# schematic.net
KiCad netlist of a schematic drawn in EAGLE
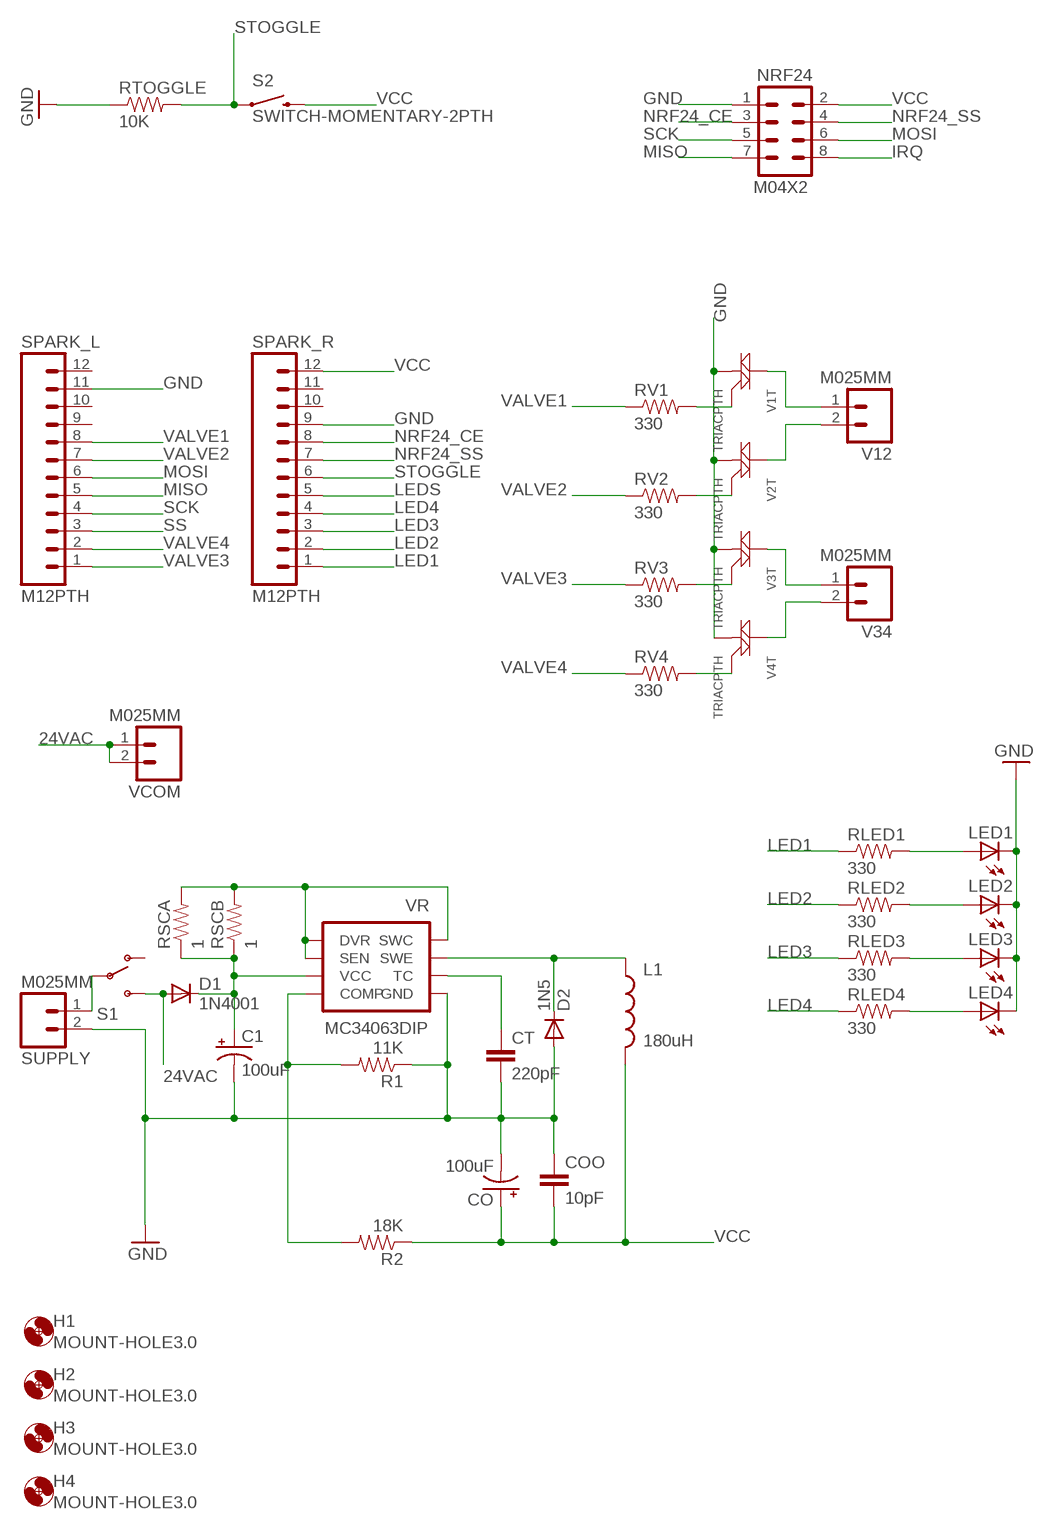
[diagram p0: schematic, sheet 1]

(export (version "E")
  (design (tool "Eeschema 10.0.6"))
  (components
    (comp (ref "C1")
      (value "100uF")
      (footprint "eagle-import:E3,5-8")
      (libsource (lib "eagle-import") (part "CPOL-USE3.5-8"))
    )
    (comp (ref "CO")
      (value "100uF")
      (footprint "eagle-import:CPOL-RADIAL-100UF-25V")
      (libsource (lib "eagle-import") (part "CAP_POLPTH1"))
    )
    (comp (ref "COO")
      (value "10pF")
      (footprint "eagle-import:CAP-PTH-5MM")
      (libsource (lib "eagle-import") (part "CAPPTH1"))
    )
    (comp (ref "CT")
      (value "220pF")
      (footprint "eagle-import:CAP-PTH-5MM")
      (libsource (lib "eagle-import") (part "CAPPTH1"))
    )
    (comp (ref "D1")
      (value "1N4001")
      (footprint "eagle-import:DIODE-1N4001")
      (libsource (lib "eagle-import") (part "DIODEPTH"))
    )
    (comp (ref "D2")
      (value "1N5")
      (footprint "eagle-import:DIODE-1N4001")
      (libsource (lib "eagle-import") (part "DIODEPTH"))
    )
    (comp (ref "H1")
      (value "MOUNT-HOLE3.0")
      (footprint "eagle-import:3,0")
      (libsource (lib "eagle-import") (part "MOUNT-HOLE3.0"))
    )
    (comp (ref "H2")
      (value "MOUNT-HOLE3.0")
      (footprint "eagle-import:3,0")
      (libsource (lib "eagle-import") (part "MOUNT-HOLE3.0"))
    )
    (comp (ref "H3")
      (value "MOUNT-HOLE3.0")
      (footprint "eagle-import:3,0")
      (libsource (lib "eagle-import") (part "MOUNT-HOLE3.0"))
    )
    (comp (ref "H4")
      (value "MOUNT-HOLE3.0")
      (footprint "eagle-import:3,0")
      (libsource (lib "eagle-import") (part "MOUNT-HOLE3.0"))
    )
    (comp (ref "L1")
      (value "180uH")
      (footprint "eagle-import:RLB0912")
      (libsource (lib "eagle-import") (part "INDUCTORRLB0912"))
    )
    (comp (ref "LED1")
      (value "LED3MM")
      (footprint "eagle-import:LED3MM")
      (libsource (lib "eagle-import") (part "LED3MM"))
    )
    (comp (ref "LED2")
      (value "LED3MM")
      (footprint "eagle-import:LED3MM")
      (libsource (lib "eagle-import") (part "LED3MM"))
    )
    (comp (ref "LED3")
      (value "LED3MM")
      (footprint "eagle-import:LED3MM")
      (libsource (lib "eagle-import") (part "LED3MM"))
    )
    (comp (ref "LED4")
      (value "LED3MM")
      (footprint "eagle-import:LED3MM")
      (libsource (lib "eagle-import") (part "LED3MM"))
    )
    (comp (ref "NRF24")
      (value "M04X2")
      (footprint "eagle-import:2X4")
      (libsource (lib "eagle-import") (part "M04X2"))
    )
    (comp (ref "R1")
      (value "11K")
      (footprint "eagle-import:AXIAL-0.3")
      (libsource (lib "eagle-import") (part "RESISTORAXIAL-0.3"))
    )
    (comp (ref "R2")
      (value "18K")
      (footprint "eagle-import:AXIAL-0.3")
      (libsource (lib "eagle-import") (part "RESISTORAXIAL-0.3"))
    )
    (comp (ref "RLED1")
      (value "330")
      (footprint "eagle-import:AXIAL-0.3")
      (libsource (lib "eagle-import") (part "RESISTORAXIAL-0.3"))
    )
    (comp (ref "RLED2")
      (value "330")
      (footprint "eagle-import:AXIAL-0.3")
      (libsource (lib "eagle-import") (part "RESISTORAXIAL-0.3"))
    )
    (comp (ref "RLED3")
      (value "330")
      (footprint "eagle-import:AXIAL-0.3")
      (libsource (lib "eagle-import") (part "RESISTORAXIAL-0.3"))
    )
    (comp (ref "RLED4")
      (value "330")
      (footprint "eagle-import:AXIAL-0.3")
      (libsource (lib "eagle-import") (part "RESISTORAXIAL-0.3"))
    )
    (comp (ref "RSCA")
      (value "1")
      (footprint "eagle-import:AXIAL-0.3")
      (libsource (lib "eagle-import") (part "RESISTORAXIAL-0.3"))
    )
    (comp (ref "RSCB")
      (value "1")
      (footprint "eagle-import:AXIAL-0.3")
      (libsource (lib "eagle-import") (part "RESISTORAXIAL-0.3"))
    )
    (comp (ref "RTOGGLE")
      (value "10K")
      (footprint "eagle-import:AXIAL-0.3")
      (libsource (lib "eagle-import") (part "RESISTORAXIAL-0.3"))
    )
    (comp (ref "RV1")
      (value "330")
      (footprint "eagle-import:AXIAL-0.3")
      (libsource (lib "eagle-import") (part "RESISTORAXIAL-0.3"))
    )
    (comp (ref "RV2")
      (value "330")
      (footprint "eagle-import:AXIAL-0.3")
      (libsource (lib "eagle-import") (part "RESISTORAXIAL-0.3"))
    )
    (comp (ref "RV3")
      (value "330")
      (footprint "eagle-import:AXIAL-0.3")
      (libsource (lib "eagle-import") (part "RESISTORAXIAL-0.3"))
    )
    (comp (ref "RV4")
      (value "330")
      (footprint "eagle-import:AXIAL-0.3")
      (libsource (lib "eagle-import") (part "RESISTORAXIAL-0.3"))
    )
    (comp (ref "S1")
      (value "SWITCH-SPDTPTH")
      (footprint "eagle-import:SWITCH-SPDT")
      (libsource (lib "eagle-import") (part "SWITCH-SPDTPTH"))
    )
    (comp (ref "S2")
      (value "SWITCH-MOMENTARY-2PTH")
      (footprint "eagle-import:TACTILE-PTH")
      (libsource (lib "eagle-import") (part "SWITCH-MOMENTARY-2PTH"))
    )
    (comp (ref "SPARK_L")
      (value "M12PTH")
      (footprint "eagle-import:1X12")
      (libsource (lib "eagle-import") (part "M12PTH"))
    )
    (comp (ref "SPARK_R")
      (value "M12PTH")
      (footprint "eagle-import:1X12")
      (libsource (lib "eagle-import") (part "M12PTH"))
    )
    (comp (ref "SUPPLY")
      (value "M025MM")
      (footprint "eagle-import:SCREWTERMINAL-5MM-2")
      (libsource (lib "eagle-import") (part "M025MM"))
    )
    (comp (ref "V1T")
      (value "TRIACPTH")
      (footprint "eagle-import:TO-92")
      (libsource (lib "eagle-import") (part "TRIACPTH"))
    )
    (comp (ref "V2T")
      (value "TRIACPTH")
      (footprint "eagle-import:TO-92")
      (libsource (lib "eagle-import") (part "TRIACPTH"))
    )
    (comp (ref "V3T")
      (value "TRIACPTH")
      (footprint "eagle-import:TO-92")
      (libsource (lib "eagle-import") (part "TRIACPTH"))
    )
    (comp (ref "V4T")
      (value "TRIACPTH")
      (footprint "eagle-import:TO-92")
      (libsource (lib "eagle-import") (part "TRIACPTH"))
    )
    (comp (ref "V12")
      (value "M025MM")
      (footprint "eagle-import:SCREWTERMINAL-5MM-2")
      (libsource (lib "eagle-import") (part "M025MM"))
    )
    (comp (ref "V34")
      (value "M025MM")
      (footprint "eagle-import:SCREWTERMINAL-5MM-2")
      (libsource (lib "eagle-import") (part "M025MM"))
    )
    (comp (ref "VCOM")
      (value "M025MM")
      (footprint "eagle-import:SCREWTERMINAL-5MM-2")
      (libsource (lib "eagle-import") (part "M025MM"))
    )
    (comp (ref "VR")
      (value "MC34063DIP")
      (footprint "eagle-import:DIP-08")
      (libsource (lib "eagle-import") (part "MC34063DIP"))
    )
  )
  (nets
    (net (code "1") (name "/24VAC") (class "Default")
      (node (ref "D1") (pin "A") (pinfunction "A_A") (pintype "passive"))
      (node (ref "S1") (pin "3") (pinfunction "S_3") (pintype "passive"))
      (node (ref "VCOM") (pin "1") (pinfunction "1_1") (pintype "passive"))
      (node (ref "VCOM") (pin "2") (pinfunction "2_2") (pintype "passive"))
    )
    (net (code "2") (name "/IRQ") (class "Default")
      (node (ref "NRF24") (pin "8") (pinfunction "8_8") (pintype "passive"))
    )
    (net (code "3") (name "/LED1") (class "Default")
      (node (ref "RLED1") (pin "P$1") (pinfunction "1_P$1") (pintype "passive"))
      (node (ref "SPARK_R") (pin "1") (pinfunction "1_1") (pintype "passive"))
    )
    (net (code "4") (name "/LED2") (class "Default")
      (node (ref "RLED2") (pin "P$1") (pinfunction "1_P$1") (pintype "passive"))
      (node (ref "SPARK_R") (pin "2") (pinfunction "2_2") (pintype "passive"))
    )
    (net (code "5") (name "/LED3") (class "Default")
      (node (ref "RLED3") (pin "P$1") (pinfunction "1_P$1") (pintype "passive"))
      (node (ref "SPARK_R") (pin "3") (pinfunction "3_3") (pintype "passive"))
    )
    (net (code "6") (name "/LED4") (class "Default")
      (node (ref "RLED4") (pin "P$1") (pinfunction "1_P$1") (pintype "passive"))
      (node (ref "SPARK_R") (pin "4") (pinfunction "4_4") (pintype "passive"))
    )
    (net (code "7") (name "/LEDS") (class "Default")
      (node (ref "SPARK_R") (pin "5") (pinfunction "5_5") (pintype "passive"))
    )
    (net (code "8") (name "/MISO") (class "Default")
      (node (ref "NRF24") (pin "7") (pinfunction "7_7") (pintype "passive"))
      (node (ref "SPARK_L") (pin "5") (pinfunction "5_5") (pintype "passive"))
    )
    (net (code "9") (name "/MOSI") (class "Default")
      (node (ref "NRF24") (pin "6") (pinfunction "6_6") (pintype "passive"))
      (node (ref "SPARK_L") (pin "6") (pinfunction "6_6") (pintype "passive"))
    )
    (net (code "10") (name "/NRF24_CE") (class "Default")
      (node (ref "NRF24") (pin "3") (pinfunction "3_3") (pintype "passive"))
      (node (ref "SPARK_R") (pin "8") (pinfunction "8_8") (pintype "passive"))
    )
    (net (code "11") (name "/NRF24_SS") (class "Default")
      (node (ref "NRF24") (pin "4") (pinfunction "4_4") (pintype "passive"))
      (node (ref "SPARK_R") (pin "7") (pinfunction "7_7") (pintype "passive"))
    )
    (net (code "12") (name "/SCK") (class "Default")
      (node (ref "NRF24") (pin "5") (pinfunction "5_5") (pintype "passive"))
      (node (ref "SPARK_L") (pin "4") (pinfunction "4_4") (pintype "passive"))
    )
    (net (code "13") (name "/SS") (class "Default")
      (node (ref "SPARK_L") (pin "3") (pinfunction "3_3") (pintype "passive"))
    )
    (net (code "14") (name "/STOGGLE") (class "Default")
      (node (ref "RTOGGLE") (pin "P$2") (pinfunction "2_P$2") (pintype "passive"))
      (node (ref "S2") (pin "1") (pinfunction "1_1") (pintype "passive"))
      (node (ref "SPARK_R") (pin "6") (pinfunction "6_6") (pintype "passive"))
    )
    (net (code "15") (name "/VALVE1") (class "Default")
      (node (ref "RV1") (pin "P$1") (pinfunction "1_P$1") (pintype "passive"))
      (node (ref "SPARK_L") (pin "8") (pinfunction "8_8") (pintype "passive"))
    )
    (net (code "16") (name "/VALVE2") (class "Default")
      (node (ref "RV2") (pin "P$1") (pinfunction "1_P$1") (pintype "passive"))
      (node (ref "SPARK_L") (pin "7") (pinfunction "7_7") (pintype "passive"))
    )
    (net (code "17") (name "/VALVE3") (class "Default")
      (node (ref "RV3") (pin "P$1") (pinfunction "1_P$1") (pintype "passive"))
      (node (ref "SPARK_L") (pin "1") (pinfunction "1_1") (pintype "passive"))
    )
    (net (code "18") (name "/VALVE4") (class "Default")
      (node (ref "RV4") (pin "P$1") (pinfunction "1_P$1") (pintype "passive"))
      (node (ref "SPARK_L") (pin "2") (pinfunction "2_2") (pintype "passive"))
    )
    (net (code "19") (name "/VCC") (class "Default")
      (node (ref "CO") (pin "1") (pinfunction "+_1") (pintype "passive"))
      (node (ref "COO") (pin "2") (pinfunction "2_2") (pintype "passive"))
      (node (ref "L1") (pin "2") (pinfunction "2_2") (pintype "passive"))
      (node (ref "NRF24") (pin "2") (pinfunction "2_2") (pintype "passive"))
      (node (ref "R2") (pin "P$1") (pinfunction "1_P$1") (pintype "passive"))
      (node (ref "S2") (pin "3") (pinfunction "2_3") (pintype "passive"))
      (node (ref "SPARK_R") (pin "12") (pinfunction "12_12") (pintype "passive"))
    )
    (net (code "20") (name "GND") (class "Default")
      (node (ref "C1") (pin "-") (pinfunction "-_-") (pintype "passive"))
      (node (ref "CO") (pin "2") (pinfunction "-_2") (pintype "passive"))
      (node (ref "COO") (pin "1") (pinfunction "1_1") (pintype "passive"))
      (node (ref "CT") (pin "2") (pinfunction "2_2") (pintype "passive"))
      (node (ref "D2") (pin "A") (pinfunction "A_A") (pintype "passive"))
      (node (ref "LED1") (pin "K") (pinfunction "C_K") (pintype "passive"))
      (node (ref "LED2") (pin "K") (pinfunction "C_K") (pintype "passive"))
      (node (ref "LED3") (pin "K") (pinfunction "C_K") (pintype "passive"))
      (node (ref "LED4") (pin "K") (pinfunction "C_K") (pintype "passive"))
      (node (ref "NRF24") (pin "1") (pinfunction "1_1") (pintype "passive"))
      (node (ref "R1") (pin "P$1") (pinfunction "1_P$1") (pintype "passive"))
      (node (ref "RTOGGLE") (pin "P$1") (pinfunction "1_P$1") (pintype "passive"))
      (node (ref "SPARK_L") (pin "11") (pinfunction "11_11") (pintype "passive"))
      (node (ref "SPARK_R") (pin "9") (pinfunction "9_9") (pintype "passive"))
      (node (ref "SUPPLY") (pin "2") (pinfunction "2_2") (pintype "passive"))
      (node (ref "V1T") (pin "1") (pinfunction "M1_1") (pintype "bidirectional"))
      (node (ref "V2T") (pin "1") (pinfunction "M1_1") (pintype "bidirectional"))
      (node (ref "V3T") (pin "1") (pinfunction "M1_1") (pintype "bidirectional"))
      (node (ref "V4T") (pin "1") (pinfunction "M1_1") (pintype "bidirectional"))
      (node (ref "VR") (pin "4") (pinfunction "GND_4") (pintype "bidirectional"))
    )
    (net (code "21") (name "Net-(R1-2)") (class "Default")
      (node (ref "R1") (pin "P$2") (pinfunction "2_P$2") (pintype "passive"))
      (node (ref "R2") (pin "P$2") (pinfunction "2_P$2") (pintype "passive"))
      (node (ref "VR") (pin "5") (pinfunction "COMP_5") (pintype "bidirectional"))
    )
    (net (code "22") (name "Net-(RLED1-2)") (class "Default")
      (node (ref "LED1") (pin "A") (pinfunction "A_A") (pintype "passive"))
      (node (ref "RLED1") (pin "P$2") (pinfunction "2_P$2") (pintype "passive"))
    )
    (net (code "23") (name "Net-(RLED2-2)") (class "Default")
      (node (ref "LED2") (pin "A") (pinfunction "A_A") (pintype "passive"))
      (node (ref "RLED2") (pin "P$2") (pinfunction "2_P$2") (pintype "passive"))
    )
    (net (code "24") (name "Net-(RLED3-2)") (class "Default")
      (node (ref "LED3") (pin "A") (pinfunction "A_A") (pintype "passive"))
      (node (ref "RLED3") (pin "P$2") (pinfunction "2_P$2") (pintype "passive"))
    )
    (net (code "25") (name "Net-(RLED4-2)") (class "Default")
      (node (ref "LED4") (pin "A") (pinfunction "A_A") (pintype "passive"))
      (node (ref "RLED4") (pin "P$2") (pinfunction "2_P$2") (pintype "passive"))
    )
    (net (code "26") (name "Net-(RSCA-1)") (class "Default")
      (node (ref "C1") (pin "+") (pinfunction "+_+") (pintype "passive"))
      (node (ref "D1") (pin "C") (pinfunction "C_C") (pintype "passive"))
      (node (ref "RSCA") (pin "P$1") (pinfunction "1_P$1") (pintype "passive"))
      (node (ref "RSCB") (pin "P$1") (pinfunction "1_P$1") (pintype "passive"))
      (node (ref "VR") (pin "6") (pinfunction "VCC_6") (pintype "bidirectional"))
    )
    (net (code "27") (name "Net-(RSCA-2)") (class "Default")
      (node (ref "RSCA") (pin "P$2") (pinfunction "2_P$2") (pintype "passive"))
      (node (ref "RSCB") (pin "P$2") (pinfunction "2_P$2") (pintype "passive"))
      (node (ref "VR") (pin "1") (pinfunction "SWC_1") (pintype "bidirectional"))
      (node (ref "VR") (pin "7") (pinfunction "SEN_7") (pintype "bidirectional"))
      (node (ref "VR") (pin "8") (pinfunction "DVR_8") (pintype "bidirectional"))
    )
    (net (code "28") (name "Net-(RV1-2)") (class "Default")
      (node (ref "RV1") (pin "P$2") (pinfunction "2_P$2") (pintype "passive"))
      (node (ref "V1T") (pin "2") (pinfunction "G_2") (pintype "bidirectional"))
    )
    (net (code "29") (name "Net-(RV2-2)") (class "Default")
      (node (ref "RV2") (pin "P$2") (pinfunction "2_P$2") (pintype "passive"))
      (node (ref "V2T") (pin "2") (pinfunction "G_2") (pintype "bidirectional"))
    )
    (net (code "30") (name "Net-(RV3-2)") (class "Default")
      (node (ref "RV3") (pin "P$2") (pinfunction "2_P$2") (pintype "passive"))
      (node (ref "V3T") (pin "2") (pinfunction "G_2") (pintype "bidirectional"))
    )
    (net (code "31") (name "Net-(RV4-2)") (class "Default")
      (node (ref "RV4") (pin "P$2") (pinfunction "2_P$2") (pintype "passive"))
      (node (ref "V4T") (pin "2") (pinfunction "G_2") (pintype "bidirectional"))
    )
    (net (code "32") (name "Net-(S1-P)") (class "Default")
      (node (ref "S1") (pin "2") (pinfunction "P_2") (pintype "passive"))
      (node (ref "SUPPLY") (pin "1") (pinfunction "1_1") (pintype "passive"))
    )
    (net (code "33") (name "Net-(V1T-M2)") (class "Default")
      (node (ref "V12") (pin "1") (pinfunction "1_1") (pintype "passive"))
      (node (ref "V1T") (pin "3") (pinfunction "M2_3") (pintype "bidirectional"))
    )
    (net (code "34") (name "Net-(V2T-M2)") (class "Default")
      (node (ref "V12") (pin "2") (pinfunction "2_2") (pintype "passive"))
      (node (ref "V2T") (pin "3") (pinfunction "M2_3") (pintype "bidirectional"))
    )
    (net (code "35") (name "Net-(V3T-M2)") (class "Default")
      (node (ref "V34") (pin "1") (pinfunction "1_1") (pintype "passive"))
      (node (ref "V3T") (pin "3") (pinfunction "M2_3") (pintype "bidirectional"))
    )
    (net (code "36") (name "Net-(V4T-M2)") (class "Default")
      (node (ref "V34") (pin "2") (pinfunction "2_2") (pintype "passive"))
      (node (ref "V4T") (pin "3") (pinfunction "M2_3") (pintype "bidirectional"))
    )
    (net (code "37") (name "Net-(VR-SWE)") (class "Default")
      (node (ref "D2") (pin "C") (pinfunction "C_C") (pintype "passive"))
      (node (ref "L1") (pin "1") (pinfunction "1_1") (pintype "passive"))
      (node (ref "VR") (pin "2") (pinfunction "SWE_2") (pintype "bidirectional"))
    )
    (net (code "38") (name "Net-(VR-TC)") (class "Default")
      (node (ref "CT") (pin "1") (pinfunction "1_1") (pintype "passive"))
      (node (ref "VR") (pin "3") (pinfunction "TC_3") (pintype "bidirectional"))
    )
    (net (code "39") (name "unconnected-(S1-O-Pad1)") (class "Default")
      (node (ref "S1") (pin "1") (pinfunction "O_1") (pintype "passive"))
    )
    (net (code "40") (name "unconnected-(SPARK_L-Pad9)") (class "Default")
      (node (ref "SPARK_L") (pin "9") (pinfunction "9_9") (pintype "passive"))
    )
    (net (code "41") (name "unconnected-(SPARK_L-Pad10)") (class "Default")
      (node (ref "SPARK_L") (pin "10") (pinfunction "10_10") (pintype "passive"))
    )
    (net (code "42") (name "unconnected-(SPARK_L-Pad12)") (class "Default")
      (node (ref "SPARK_L") (pin "12") (pinfunction "12_12") (pintype "passive"))
    )
    (net (code "43") (name "unconnected-(SPARK_R-Pad10)") (class "Default")
      (node (ref "SPARK_R") (pin "10") (pinfunction "10_10") (pintype "passive"))
    )
    (net (code "44") (name "unconnected-(SPARK_R-Pad11)") (class "Default")
      (node (ref "SPARK_R") (pin "11") (pinfunction "11_11") (pintype "passive"))
    )
  )
)
